# GrappleRobot_ControlBoard_V1_0.net
KiCad netlist of a schematic drawn in Altium Designer
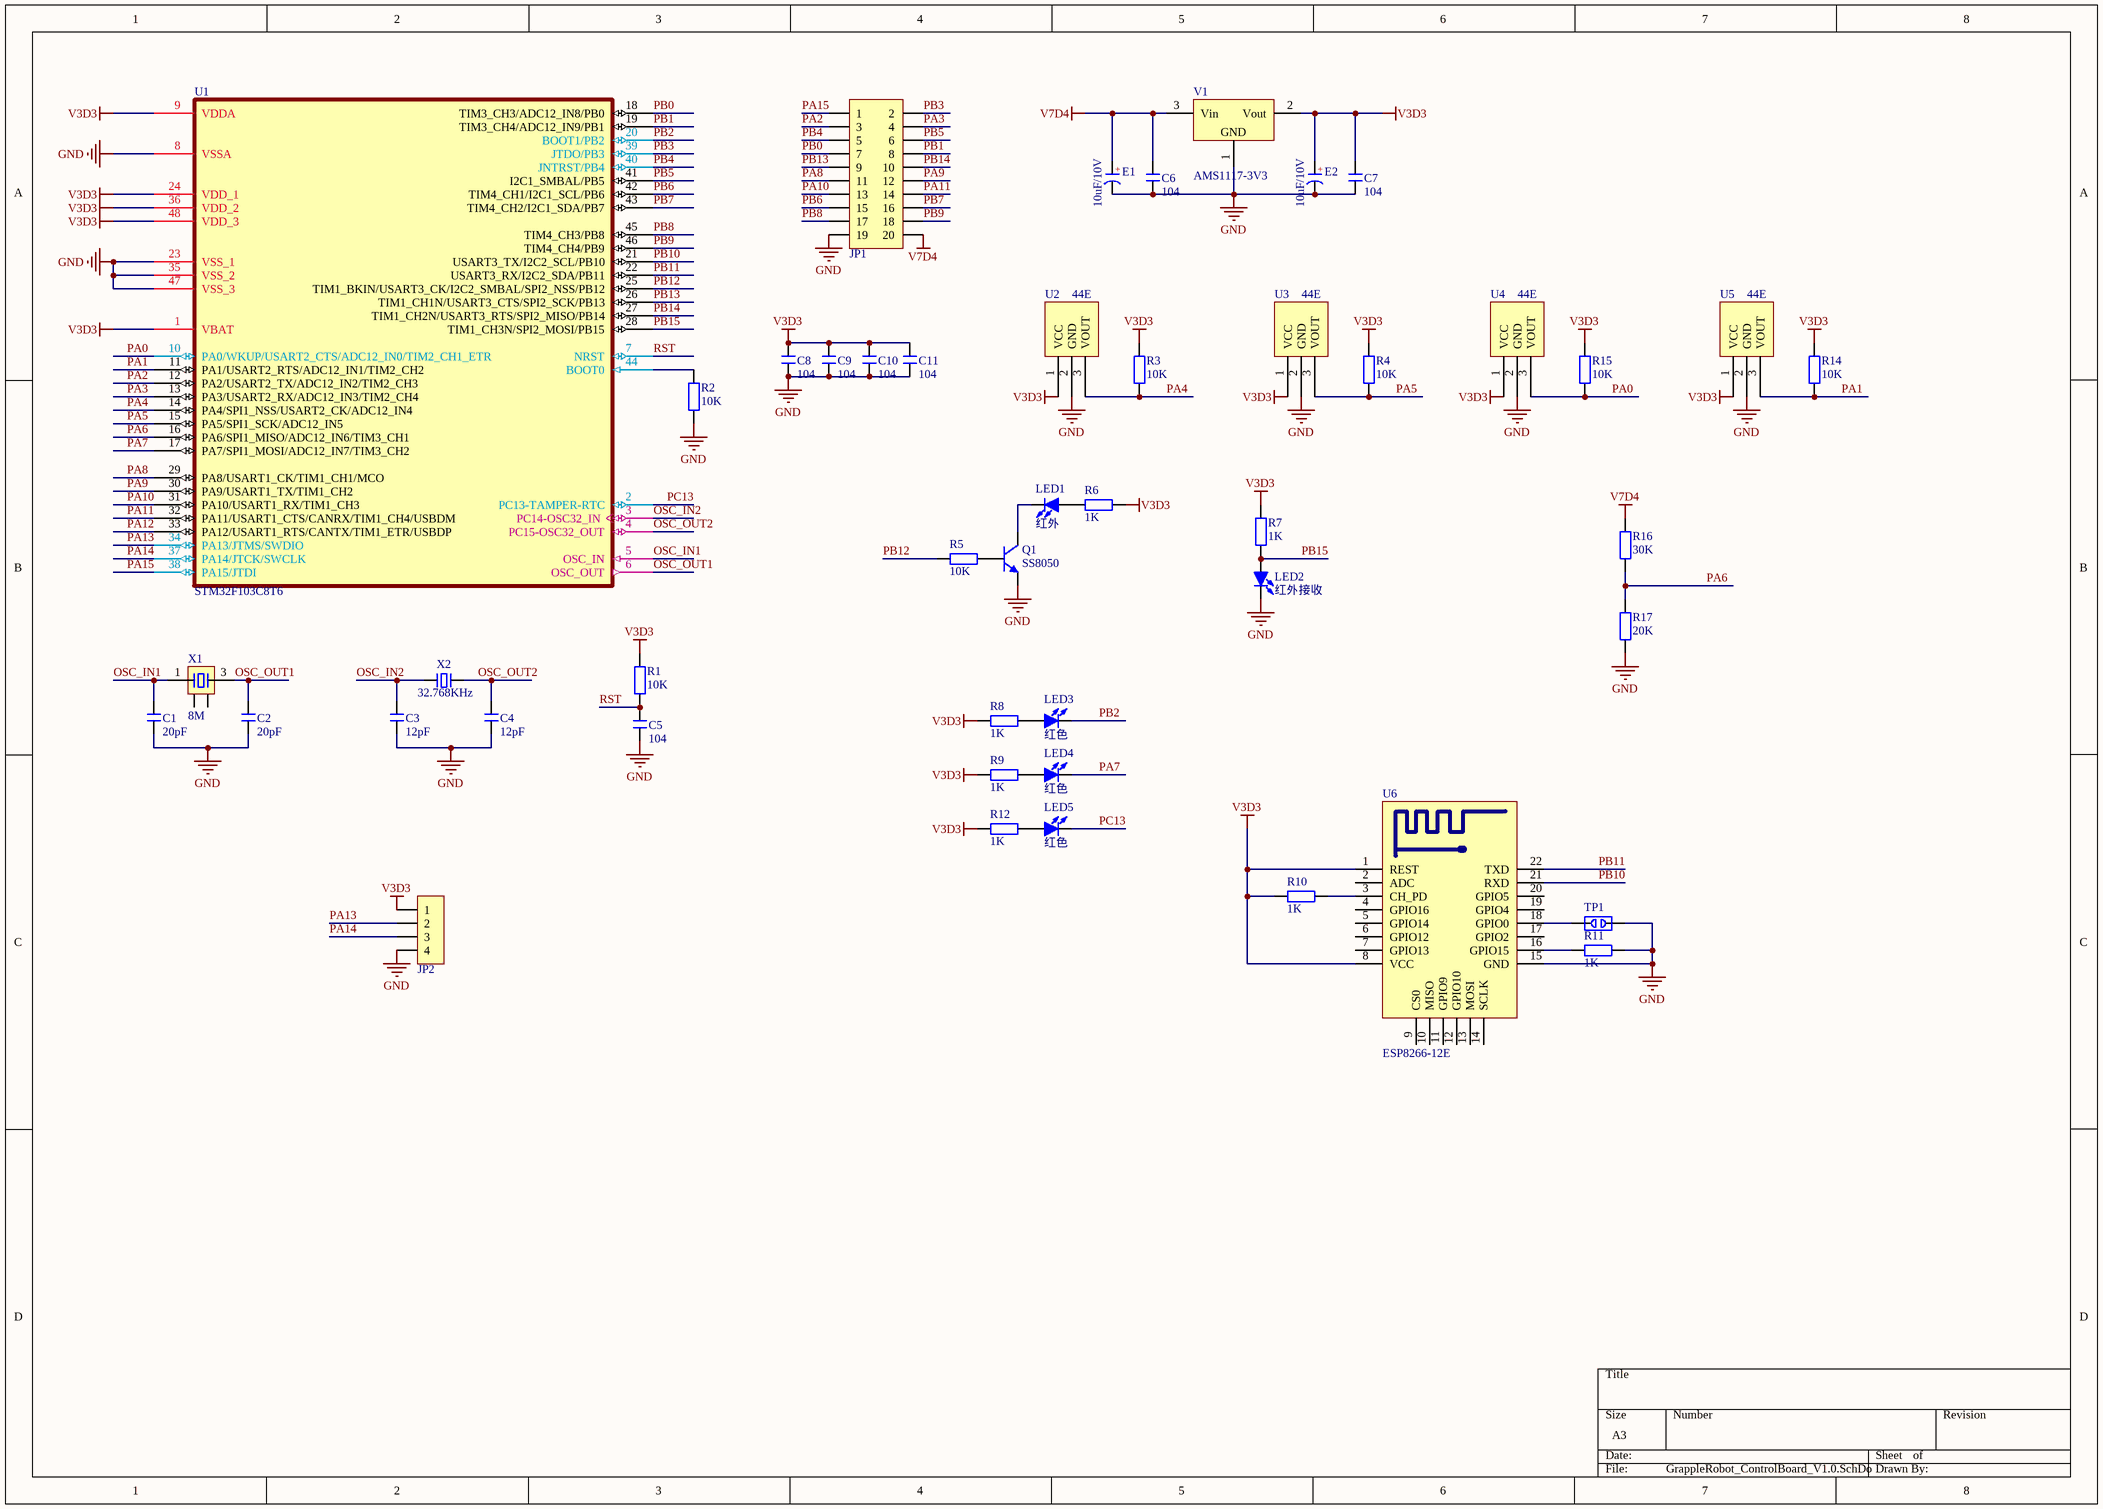
[diagram p0: GrappleRobot_ControlBoard_V1.0.SchDoc]

(export (version "E")
  (design (tool "Eeschema 10.0.6"))
  (components
    (comp (ref "C1")
      (value "20pF")
      (footprint "C 0603")
      (description "无极性贴片电容")
      (fields (field (name "版权归属") "黎明电子style"))
      (libsource (lib "电阻-电容-电感") (part "C"))
    )
    (comp (ref "C2")
      (value "20pF")
      (footprint "C 0603")
      (description "无极性贴片电容")
      (fields (field (name "版权归属") "黎明电子style"))
      (libsource (lib "电阻-电容-电感") (part "C"))
    )
    (comp (ref "C3")
      (value "12pF")
      (footprint "C 0603")
      (description "无极性贴片电容")
      (fields (field (name "版权归属") "黎明电子style"))
      (libsource (lib "电阻-电容-电感") (part "C"))
    )
    (comp (ref "C4")
      (value "12pF")
      (footprint "C 0603")
      (description "无极性贴片电容")
      (fields (field (name "版权归属") "黎明电子style"))
      (libsource (lib "电阻-电容-电感") (part "C"))
    )
    (comp (ref "C5")
      (value "104")
      (footprint "C 0603")
      (description "无极性贴片电容")
      (fields (field (name "版权归属") "黎明电子style"))
      (libsource (lib "电阻-电容-电感") (part "C"))
    )
    (comp (ref "C6")
      (value "104")
      (footprint "C 0603")
      (description "无极性贴片电容")
      (fields (field (name "版权归属") "黎明电子style"))
      (libsource (lib "电阻-电容-电感") (part "C"))
    )
    (comp (ref "C7")
      (value "104")
      (footprint "C 0603")
      (description "无极性贴片电容")
      (fields (field (name "版权归属") "黎明电子style"))
      (libsource (lib "电阻-电容-电感") (part "C"))
    )
    (comp (ref "C8")
      (value "104")
      (footprint "C 0603")
      (description "无极性贴片电容")
      (fields (field (name "版权归属") "黎明电子style"))
      (libsource (lib "电阻-电容-电感") (part "C"))
    )
    (comp (ref "C9")
      (value "104")
      (footprint "C 0603")
      (description "无极性贴片电容")
      (fields (field (name "版权归属") "黎明电子style"))
      (libsource (lib "电阻-电容-电感") (part "C"))
    )
    (comp (ref "C10")
      (value "104")
      (footprint "C 0603")
      (description "无极性贴片电容")
      (fields (field (name "版权归属") "黎明电子style"))
      (libsource (lib "电阻-电容-电感") (part "C"))
    )
    (comp (ref "C11")
      (value "104")
      (footprint "C 0603")
      (description "无极性贴片电容")
      (fields (field (name "版权归属") "黎明电子style"))
      (libsource (lib "电阻-电容-电感") (part "C"))
    )
    (comp (ref "E1")
      (value "10uF/10V")
      (footprint "C 1206")
      (description "贴片电解电容")
      (fields (field (name "版权归属") "黎明电子style"))
      (libsource (lib "电阻-电容-电感") (part "C-CM"))
    )
    (comp (ref "E2")
      (value "10uF/10V")
      (footprint "C 1206")
      (description "贴片电解电容")
      (fields (field (name "版权归属") "黎明电子style"))
      (libsource (lib "电阻-电容-电感") (part "C-CM"))
    )
    (comp (ref "JP1")
      (value "Header 2X10")
      (footprint "HDR-10X2")
      (description "10*2P接插件")
      (fields (field (name "版权归属") "黎明电子style"))
      (libsource (lib "接插件") (part "Header 10X2"))
    )
    (comp (ref "JP2")
      (value "HDR-1X4")
      (footprint "HDR-1X4")
      (description "4P接插件")
      (fields (field (name "版权归属") "黎明电子style"))
      (libsource (lib "接插件") (part "Header 4"))
    )
    (comp (ref "LED1")
      (value "红外")
      (footprint "LED 5MM-B")
      (description "5mm插件LED")
      (fields (field (name "版权归属") "黎明电子style"))
      (libsource (lib "LED") (part "LED-5MM"))
    )
    (comp (ref "LED2")
      (value "红外接收")
      (footprint "LED 5MM-B")
      (description "5mm插件LED")
      (fields (field (name "版权归属") "黎明电子style"))
      (libsource (lib "LED") (part "LED-5MM"))
    )
    (comp (ref "LED3")
      (value "红色")
      (footprint "LED 0603R")
      (description "5mm插件LED")
      (fields (field (name "版权归属") "黎明电子style"))
      (libsource (lib "LED") (part "LED-5MM"))
    )
    (comp (ref "LED4")
      (value "红色")
      (footprint "LED 0603R")
      (description "5mm插件LED")
      (fields (field (name "版权归属") "黎明电子style"))
      (libsource (lib "LED") (part "LED-5MM"))
    )
    (comp (ref "LED5")
      (value "红色")
      (footprint "LED 0603R")
      (description "5mm插件LED")
      (fields (field (name "版权归属") "黎明电子style"))
      (libsource (lib "LED") (part "LED-5MM"))
    )
    (comp (ref "Q1")
      (value "SS8050")
      (footprint "SOT23-3N")
      (description "高频放大-NPN型")
      (fields (field (name "版权归属") "黎明电子style"))
      (libsource (lib "三极管") (part "8050-SMD"))
    )
    (comp (ref "R1")
      (value "10K")
      (footprint "R 0603")
      (description "贴片电阻")
      (fields (field (name "版权归属") "黎明电子style"))
      (libsource (lib "电阻-电容-电感") (part "R"))
    )
    (comp (ref "R2")
      (value "10K")
      (footprint "R 0603")
      (description "贴片电阻")
      (fields (field (name "版权归属") "黎明电子style"))
      (libsource (lib "电阻-电容-电感") (part "R"))
    )
    (comp (ref "R3")
      (value "10K")
      (footprint "R 0603")
      (description "贴片电阻")
      (fields (field (name "版权归属") "黎明电子style"))
      (libsource (lib "电阻-电容-电感") (part "R"))
    )
    (comp (ref "R4")
      (value "10K")
      (footprint "R 0603")
      (description "贴片电阻")
      (fields (field (name "版权归属") "黎明电子style"))
      (libsource (lib "电阻-电容-电感") (part "R"))
    )
    (comp (ref "R5")
      (value "10K")
      (footprint "R 0603")
      (description "贴片电阻")
      (fields (field (name "版权归属") "黎明电子style"))
      (libsource (lib "电阻-电容-电感") (part "R"))
    )
    (comp (ref "R6")
      (value "1K")
      (footprint "R 0603")
      (description "贴片电阻")
      (fields (field (name "版权归属") "黎明电子style"))
      (libsource (lib "电阻-电容-电感") (part "R"))
    )
    (comp (ref "R7")
      (value "1K")
      (footprint "R 0603")
      (description "贴片电阻")
      (fields (field (name "版权归属") "黎明电子style"))
      (libsource (lib "电阻-电容-电感") (part "R"))
    )
    (comp (ref "R8")
      (value "1K")
      (footprint "R 0603")
      (description "贴片电阻")
      (fields (field (name "版权归属") "黎明电子style"))
      (libsource (lib "电阻-电容-电感") (part "R"))
    )
    (comp (ref "R9")
      (value "1K")
      (footprint "R 0603")
      (description "贴片电阻")
      (fields (field (name "版权归属") "黎明电子style"))
      (libsource (lib "电阻-电容-电感") (part "R"))
    )
    (comp (ref "R10")
      (value "1K")
      (footprint "R 0603")
      (description "贴片电阻")
      (fields (field (name "版权归属") "黎明电子style"))
      (libsource (lib "电阻-电容-电感") (part "R"))
    )
    (comp (ref "R11")
      (value "1K")
      (footprint "R 0603")
      (description "贴片电阻")
      (fields (field (name "版权归属") "黎明电子style"))
      (libsource (lib "电阻-电容-电感") (part "R"))
    )
    (comp (ref "R12")
      (value "1K")
      (footprint "R 0603")
      (description "贴片电阻")
      (fields (field (name "版权归属") "黎明电子style"))
      (libsource (lib "电阻-电容-电感") (part "R"))
    )
    (comp (ref "R14")
      (value "10K")
      (footprint "R 0603")
      (description "贴片电阻")
      (fields (field (name "版权归属") "黎明电子style"))
      (libsource (lib "电阻-电容-电感") (part "R"))
    )
    (comp (ref "R15")
      (value "10K")
      (footprint "R 0603")
      (description "贴片电阻")
      (fields (field (name "版权归属") "黎明电子style"))
      (libsource (lib "电阻-电容-电感") (part "R"))
    )
    (comp (ref "R16")
      (value "30K")
      (footprint "R 0603")
      (description "贴片电阻")
      (fields (field (name "版权归属") "黎明电子style"))
      (libsource (lib "电阻-电容-电感") (part "R"))
    )
    (comp (ref "R17")
      (value "20K")
      (footprint "R 0603")
      (description "贴片电阻")
      (fields (field (name "版权归属") "黎明电子style"))
      (libsource (lib "电阻-电容-电感") (part "R"))
    )
    (comp (ref "TP1")
      (value "~")
      (footprint "DEBUG PAD2")
      (description "调试断点焊盘")
      (fields (field (name "版权归属") "黎明电子style"))
      (libsource (lib "未分类器件") (part "DEBUG"))
    )
    (comp (ref "U1")
      (value "STM32F103C8T6")
      (footprint "stm8&stm32:LQFP48")
      (description "STM32 ARM-based 32-bit MCU with 64 Kbytes Flash, 48-pin LQFP, Industrial Temperature")
      (fields (field (name "PUBLISHER") "*"))
      (libsource (lib "stm8&stm32") (part "STM32F103C8T6"))
    )
    (comp (ref "U2") (value "44E") (footprint "SOT23-3N") (libsource (lib "LoveX") (part "44E")))
    (comp (ref "U3") (value "44E") (footprint "SOT23-3N") (libsource (lib "LoveX") (part "44E")))
    (comp (ref "U4") (value "44E") (footprint "SOT23-3N") (libsource (lib "LoveX") (part "44E")))
    (comp (ref "U5") (value "44E") (footprint "SOT23-3N") (libsource (lib "LoveX") (part "44E")))
    (comp (ref "U6")
      (value "ESP8266-12E")
      (footprint "ESP_12E")
      (description "串口 WIFI模块，ESP-12E")
      (fields (field (name "版权归属") "黎明电子style"))
      (libsource (lib "模块") (part "ESP8266-12E"))
    )
    (comp (ref "V1")
      (value "AMS1117-3V3")
      (footprint "SOT223_N")
      (description "三端稳压芯片")
      (fields (field (name "版权归属") "黎明电子style"))
      (libsource (lib "IC芯片") (part "AMS1117"))
    )
    (comp (ref "X1")
      (value "8M")
      (footprint "XTAL-5032")
      (description "4脚晶振")
      (fields (field (name "版权归属") "黎明电子style"))
      (libsource (lib "保险丝-晶振") (part "XTAL-4"))
    )
    (comp (ref "X2")
      (value "32.768KHz")
      (footprint "XTAL-3215")
      (description "2脚晶振")
      (fields (field (name "版权归属") "黎明电子style"))
      (libsource (lib "保险丝-晶振") (part "XTAL-2"))
    )
  )
  (nets
    (net (code "1") (name "/OSC_IN1") (class "Default")
      (node (ref "C1") (pin "2") (pinfunction "2_2") (pintype "passive"))
      (node (ref "U1") (pin "5") (pinfunction "OSC_IN_5") (pintype "input"))
      (node (ref "X1") (pin "1") (pinfunction "1_1") (pintype "passive"))
    )
    (net (code "2") (name "/OSC_IN2") (class "Default")
      (node (ref "C3") (pin "2") (pinfunction "2_2") (pintype "passive"))
      (node (ref "U1") (pin "3") (pinfunction "PC14-OSC32_IN_3") (pintype "bidirectional"))
      (node (ref "X2") (pin "1") (pinfunction "1_1") (pintype "passive"))
    )
    (net (code "3") (name "/OSC_OUT1") (class "Default")
      (node (ref "C2") (pin "2") (pinfunction "2_2") (pintype "passive"))
      (node (ref "U1") (pin "6") (pinfunction "OSC_OUT_6") (pintype "output"))
      (node (ref "X1") (pin "3") (pinfunction "3_3") (pintype "passive"))
    )
    (net (code "4") (name "/OSC_OUT2") (class "Default")
      (node (ref "C4") (pin "2") (pinfunction "2_2") (pintype "passive"))
      (node (ref "U1") (pin "4") (pinfunction "PC15-OSC32_OUT_4") (pintype "bidirectional"))
      (node (ref "X2") (pin "2") (pinfunction "2_2") (pintype "passive"))
    )
    (net (code "5") (name "/PA0") (class "Default")
      (node (ref "R15") (pin "1") (pinfunction "1_1") (pintype "passive"))
      (node (ref "U1") (pin "10") (pinfunction "PA0/WKUP/USART2_CTS/ADC12_IN0/TIM2_CH1_ETR_10") (pintype "bidirectional"))
      (node (ref "U4") (pin "3") (pinfunction "VOUT_3") (pintype "passive"))
    )
    (net (code "6") (name "/PA1") (class "Default")
      (node (ref "R14") (pin "1") (pinfunction "1_1") (pintype "passive"))
      (node (ref "U1") (pin "11") (pinfunction "PA1/USART2_RTS/ADC12_IN1/TIM2_CH2_11") (pintype "bidirectional"))
      (node (ref "U5") (pin "3") (pinfunction "VOUT_3") (pintype "passive"))
    )
    (net (code "7") (name "/PA2") (class "Default")
      (node (ref "JP1") (pin "3") (pinfunction "3_3") (pintype "passive"))
      (node (ref "U1") (pin "12") (pinfunction "PA2/USART2_TX/ADC12_IN2/TIM2_CH3_12") (pintype "bidirectional"))
    )
    (net (code "8") (name "/PA3") (class "Default")
      (node (ref "JP1") (pin "4") (pinfunction "4_4") (pintype "passive"))
      (node (ref "U1") (pin "13") (pinfunction "PA3/USART2_RX/ADC12_IN3/TIM2_CH4_13") (pintype "bidirectional"))
    )
    (net (code "9") (name "/PA4") (class "Default")
      (node (ref "R3") (pin "1") (pinfunction "1_1") (pintype "passive"))
      (node (ref "U1") (pin "14") (pinfunction "PA4/SPI1_NSS/USART2_CK/ADC12_IN4_14") (pintype "bidirectional"))
      (node (ref "U2") (pin "3") (pinfunction "VOUT_3") (pintype "passive"))
    )
    (net (code "10") (name "/PA5") (class "Default")
      (node (ref "R4") (pin "1") (pinfunction "1_1") (pintype "passive"))
      (node (ref "U1") (pin "15") (pinfunction "PA5/SPI1_SCK/ADC12_IN5_15") (pintype "bidirectional"))
      (node (ref "U3") (pin "3") (pinfunction "VOUT_3") (pintype "passive"))
    )
    (net (code "11") (name "/PA6") (class "Default")
      (node (ref "R16") (pin "2") (pinfunction "2_2") (pintype "passive"))
      (node (ref "R17") (pin "1") (pinfunction "1_1") (pintype "passive"))
      (node (ref "U1") (pin "16") (pinfunction "PA6/SPI1_MISO/ADC12_IN6/TIM3_CH1_16") (pintype "bidirectional"))
    )
    (net (code "12") (name "/PA7") (class "Default")
      (node (ref "LED4") (pin "2") (pinfunction "K_2") (pintype "passive"))
      (node (ref "U1") (pin "17") (pinfunction "PA7/SPI1_MOSI/ADC12_IN7/TIM3_CH2_17") (pintype "bidirectional"))
    )
    (net (code "13") (name "/PA8") (class "Default")
      (node (ref "JP1") (pin "11") (pinfunction "11_11") (pintype "passive"))
      (node (ref "U1") (pin "29") (pinfunction "PA8/USART1_CK/TIM1_CH1/MCO_29") (pintype "bidirectional"))
    )
    (net (code "14") (name "/PA9") (class "Default")
      (node (ref "JP1") (pin "12") (pinfunction "12_12") (pintype "passive"))
      (node (ref "U1") (pin "30") (pinfunction "PA9/USART1_TX/TIM1_CH2_30") (pintype "bidirectional"))
    )
    (net (code "15") (name "/PA10") (class "Default")
      (node (ref "JP1") (pin "13") (pinfunction "13_13") (pintype "passive"))
      (node (ref "U1") (pin "31") (pinfunction "PA10/USART1_RX/TIM1_CH3_31") (pintype "bidirectional"))
    )
    (net (code "16") (name "/PA11") (class "Default")
      (node (ref "JP1") (pin "14") (pinfunction "14_14") (pintype "passive"))
      (node (ref "U1") (pin "32") (pinfunction "PA11/USART1_CTS/CANRX/TIM1_CH4/USBDM_32") (pintype "bidirectional"))
    )
    (net (code "17") (name "/PA12") (class "Default")
      (node (ref "U1") (pin "33") (pinfunction "PA12/USART1_RTS/CANTX/TIM1_ETR/USBDP_33") (pintype "bidirectional"))
    )
    (net (code "18") (name "/PA13") (class "Default")
      (node (ref "JP2") (pin "2") (pinfunction "2_2") (pintype "passive"))
      (node (ref "U1") (pin "34") (pinfunction "PA13/JTMS/SWDIO_34") (pintype "bidirectional"))
    )
    (net (code "19") (name "/PA14") (class "Default")
      (node (ref "JP2") (pin "3") (pinfunction "3_3") (pintype "passive"))
      (node (ref "U1") (pin "37") (pinfunction "PA14/JTCK/SWCLK_37") (pintype "bidirectional"))
    )
    (net (code "20") (name "/PA15") (class "Default")
      (node (ref "JP1") (pin "1") (pinfunction "1_1") (pintype "passive"))
      (node (ref "U1") (pin "38") (pinfunction "PA15/JTDI_38") (pintype "bidirectional"))
    )
    (net (code "21") (name "/PB0") (class "Default")
      (node (ref "JP1") (pin "7") (pinfunction "7_7") (pintype "passive"))
      (node (ref "U1") (pin "18") (pinfunction "TIM3_CH3/ADC12_IN8/PB0_18") (pintype "bidirectional"))
    )
    (net (code "22") (name "/PB1") (class "Default")
      (node (ref "JP1") (pin "8") (pinfunction "8_8") (pintype "passive"))
      (node (ref "U1") (pin "19") (pinfunction "TIM3_CH4/ADC12_IN9/PB1_19") (pintype "bidirectional"))
    )
    (net (code "23") (name "/PB2") (class "Default")
      (node (ref "LED3") (pin "2") (pinfunction "K_2") (pintype "passive"))
      (node (ref "U1") (pin "20") (pinfunction "BOOT1/PB2_20") (pintype "bidirectional"))
    )
    (net (code "24") (name "/PB3") (class "Default")
      (node (ref "JP1") (pin "2") (pinfunction "2_2") (pintype "passive"))
      (node (ref "U1") (pin "39") (pinfunction "JTDO/PB3_39") (pintype "bidirectional"))
    )
    (net (code "25") (name "/PB4") (class "Default")
      (node (ref "JP1") (pin "5") (pinfunction "5_5") (pintype "passive"))
      (node (ref "U1") (pin "40") (pinfunction "JNTRST/PB4_40") (pintype "bidirectional"))
    )
    (net (code "26") (name "/PB5") (class "Default")
      (node (ref "JP1") (pin "6") (pinfunction "6_6") (pintype "passive"))
      (node (ref "U1") (pin "41") (pinfunction "I2C1_SMBAL/PB5_41") (pintype "bidirectional"))
    )
    (net (code "27") (name "/PB6") (class "Default")
      (node (ref "JP1") (pin "15") (pinfunction "15_15") (pintype "passive"))
      (node (ref "U1") (pin "42") (pinfunction "TIM4_CH1/I2C1_SCL/PB6_42") (pintype "bidirectional"))
    )
    (net (code "28") (name "/PB7") (class "Default")
      (node (ref "JP1") (pin "16") (pinfunction "16_16") (pintype "passive"))
      (node (ref "U1") (pin "43") (pinfunction "TIM4_CH2/I2C1_SDA/PB7_43") (pintype "bidirectional"))
    )
    (net (code "29") (name "/PB8") (class "Default")
      (node (ref "JP1") (pin "17") (pinfunction "17_17") (pintype "passive"))
      (node (ref "U1") (pin "45") (pinfunction "TIM4_CH3/PB8_45") (pintype "bidirectional"))
    )
    (net (code "30") (name "/PB9") (class "Default")
      (node (ref "JP1") (pin "18") (pinfunction "18_18") (pintype "passive"))
      (node (ref "U1") (pin "46") (pinfunction "TIM4_CH4/PB9_46") (pintype "bidirectional"))
    )
    (net (code "31") (name "/PB10") (class "Default")
      (node (ref "U1") (pin "21") (pinfunction "USART3_TX/I2C2_SCL/PB10_21") (pintype "bidirectional"))
      (node (ref "U6") (pin "21") (pinfunction "RXD_21") (pintype "passive"))
    )
    (net (code "32") (name "/PB11") (class "Default")
      (node (ref "U1") (pin "22") (pinfunction "USART3_RX/I2C2_SDA/PB11_22") (pintype "bidirectional"))
      (node (ref "U6") (pin "22") (pinfunction "TXD_22") (pintype "passive"))
    )
    (net (code "33") (name "/PB12") (class "Default")
      (node (ref "R5") (pin "2") (pinfunction "2_2") (pintype "passive"))
      (node (ref "U1") (pin "25") (pinfunction "TIM1_BKIN/USART3_CK/I2C2_SMBAL/SPI2_NSS/PB12_25") (pintype "bidirectional"))
    )
    (net (code "34") (name "/PB13") (class "Default")
      (node (ref "JP1") (pin "9") (pinfunction "9_9") (pintype "passive"))
      (node (ref "U1") (pin "26") (pinfunction "TIM1_CH1N/USART3_CTS/SPI2_SCK/PB13_26") (pintype "bidirectional"))
    )
    (net (code "35") (name "/PB14") (class "Default")
      (node (ref "JP1") (pin "10") (pinfunction "10_10") (pintype "passive"))
      (node (ref "U1") (pin "27") (pinfunction "TIM1_CH2N/USART3_RTS/SPI2_MISO/PB14_27") (pintype "bidirectional"))
    )
    (net (code "36") (name "/PB15") (class "Default")
      (node (ref "LED2") (pin "1") (pinfunction "A_1") (pintype "passive"))
      (node (ref "R7") (pin "2") (pinfunction "2_2") (pintype "passive"))
      (node (ref "U1") (pin "28") (pinfunction "TIM1_CH3N/SPI2_MOSI/PB15_28") (pintype "bidirectional"))
    )
    (net (code "37") (name "/PC13") (class "Default")
      (node (ref "LED5") (pin "2") (pinfunction "K_2") (pintype "passive"))
      (node (ref "U1") (pin "2") (pinfunction "PC13-TAMPER-RTC_2") (pintype "bidirectional"))
    )
    (net (code "38") (name "/RST") (class "Default")
      (node (ref "C5") (pin "2") (pinfunction "2_2") (pintype "passive"))
      (node (ref "R1") (pin "1") (pinfunction "1_1") (pintype "passive"))
      (node (ref "U1") (pin "7") (pinfunction "NRST_7") (pintype "bidirectional"))
    )
    (net (code "39") (name "GND") (class "Default")
      (node (ref "C1") (pin "1") (pinfunction "1_1") (pintype "passive"))
      (node (ref "C10") (pin "1") (pinfunction "1_1") (pintype "passive"))
      (node (ref "C11") (pin "1") (pinfunction "1_1") (pintype "passive"))
      (node (ref "C2") (pin "1") (pinfunction "1_1") (pintype "passive"))
      (node (ref "C3") (pin "1") (pinfunction "1_1") (pintype "passive"))
      (node (ref "C4") (pin "1") (pinfunction "1_1") (pintype "passive"))
      (node (ref "C5") (pin "1") (pinfunction "1_1") (pintype "passive"))
      (node (ref "C6") (pin "1") (pinfunction "1_1") (pintype "passive"))
      (node (ref "C7") (pin "1") (pinfunction "1_1") (pintype "passive"))
      (node (ref "C8") (pin "1") (pinfunction "1_1") (pintype "passive"))
      (node (ref "C9") (pin "1") (pinfunction "1_1") (pintype "passive"))
      (node (ref "E1") (pin "2") (pinfunction "K_2") (pintype "passive"))
      (node (ref "E2") (pin "2") (pinfunction "K_2") (pintype "passive"))
      (node (ref "JP1") (pin "19") (pinfunction "19_19") (pintype "passive"))
      (node (ref "JP2") (pin "4") (pinfunction "4_4") (pintype "passive"))
      (node (ref "LED2") (pin "2") (pinfunction "K_2") (pintype "passive"))
      (node (ref "Q1") (pin "2") (pinfunction "E_2") (pintype "passive"))
      (node (ref "R11") (pin "2") (pinfunction "2_2") (pintype "passive"))
      (node (ref "R17") (pin "2") (pinfunction "2_2") (pintype "passive"))
      (node (ref "R2") (pin "1") (pinfunction "1_1") (pintype "passive"))
      (node (ref "TP1") (pin "2") (pinfunction "2_2") (pintype "passive"))
      (node (ref "U1") (pin "23") (pinfunction "VSS_1_23") (pintype "power_in"))
      (node (ref "U1") (pin "35") (pinfunction "VSS_2_35") (pintype "power_in"))
      (node (ref "U1") (pin "47") (pinfunction "VSS_3_47") (pintype "power_in"))
      (node (ref "U1") (pin "8") (pinfunction "VSSA_8") (pintype "power_in"))
      (node (ref "U2") (pin "2") (pinfunction "GND_2") (pintype "passive"))
      (node (ref "U3") (pin "2") (pinfunction "GND_2") (pintype "passive"))
      (node (ref "U4") (pin "2") (pinfunction "GND_2") (pintype "passive"))
      (node (ref "U5") (pin "2") (pinfunction "GND_2") (pintype "passive"))
      (node (ref "U6") (pin "15") (pinfunction "GND_15") (pintype "passive"))
      (node (ref "V1") (pin "1") (pinfunction "GND_1") (pintype "passive"))
    )
    (net (code "40") (name "Net-(LED1-A)") (class "Default")
      (node (ref "LED1") (pin "1") (pinfunction "A_1") (pintype "passive"))
      (node (ref "R6") (pin "2") (pinfunction "2_2") (pintype "passive"))
    )
    (net (code "41") (name "Net-(LED1-K)") (class "Default")
      (node (ref "LED1") (pin "2") (pinfunction "K_2") (pintype "passive"))
      (node (ref "Q1") (pin "3") (pinfunction "C_3") (pintype "passive"))
    )
    (net (code "42") (name "Net-(LED3-A)") (class "Default")
      (node (ref "LED3") (pin "1") (pinfunction "A_1") (pintype "passive"))
      (node (ref "R8") (pin "2") (pinfunction "2_2") (pintype "passive"))
    )
    (net (code "43") (name "Net-(LED4-A)") (class "Default")
      (node (ref "LED4") (pin "1") (pinfunction "A_1") (pintype "passive"))
      (node (ref "R9") (pin "2") (pinfunction "2_2") (pintype "passive"))
    )
    (net (code "44") (name "Net-(LED5-A)") (class "Default")
      (node (ref "LED5") (pin "1") (pinfunction "A_1") (pintype "passive"))
      (node (ref "R12") (pin "2") (pinfunction "2_2") (pintype "passive"))
    )
    (net (code "45") (name "Net-(Q1-B)") (class "Default")
      (node (ref "Q1") (pin "1") (pinfunction "B_1") (pintype "passive"))
      (node (ref "R5") (pin "1") (pinfunction "1_1") (pintype "passive"))
    )
    (net (code "46") (name "Net-(U1-BOOT0)") (class "Default")
      (node (ref "R2") (pin "2") (pinfunction "2_2") (pintype "passive"))
      (node (ref "U1") (pin "44") (pinfunction "BOOT0_44") (pintype "input"))
    )
    (net (code "47") (name "Net-(U6-CH_PD)") (class "Default")
      (node (ref "R10") (pin "2") (pinfunction "2_2") (pintype "passive"))
      (node (ref "U6") (pin "3") (pinfunction "CH_PD_3") (pintype "passive"))
    )
    (net (code "48") (name "Net-(U6-GPIO0)") (class "Default")
      (node (ref "TP1") (pin "1") (pinfunction "1_1") (pintype "passive"))
      (node (ref "U6") (pin "18") (pinfunction "GPIO0_18") (pintype "passive"))
    )
    (net (code "49") (name "Net-(U6-GPIO15)") (class "Default")
      (node (ref "R11") (pin "1") (pinfunction "1_1") (pintype "passive"))
      (node (ref "U6") (pin "16") (pinfunction "GPIO15_16") (pintype "passive"))
    )
    (net (code "50") (name "V3D3") (class "Default")
      (node (ref "C10") (pin "2") (pinfunction "2_2") (pintype "passive"))
      (node (ref "C11") (pin "2") (pinfunction "2_2") (pintype "passive"))
      (node (ref "C7") (pin "2") (pinfunction "2_2") (pintype "passive"))
      (node (ref "C8") (pin "2") (pinfunction "2_2") (pintype "passive"))
      (node (ref "C9") (pin "2") (pinfunction "2_2") (pintype "passive"))
      (node (ref "E2") (pin "1") (pinfunction "A_1") (pintype "passive"))
      (node (ref "JP2") (pin "1") (pinfunction "1_1") (pintype "passive"))
      (node (ref "R1") (pin "2") (pinfunction "2_2") (pintype "passive"))
      (node (ref "R10") (pin "1") (pinfunction "1_1") (pintype "passive"))
      (node (ref "R12") (pin "1") (pinfunction "1_1") (pintype "passive"))
      (node (ref "R14") (pin "2") (pinfunction "2_2") (pintype "passive"))
      (node (ref "R15") (pin "2") (pinfunction "2_2") (pintype "passive"))
      (node (ref "R3") (pin "2") (pinfunction "2_2") (pintype "passive"))
      (node (ref "R4") (pin "2") (pinfunction "2_2") (pintype "passive"))
      (node (ref "R6") (pin "1") (pinfunction "1_1") (pintype "passive"))
      (node (ref "R7") (pin "1") (pinfunction "1_1") (pintype "passive"))
      (node (ref "R8") (pin "1") (pinfunction "1_1") (pintype "passive"))
      (node (ref "R9") (pin "1") (pinfunction "1_1") (pintype "passive"))
      (node (ref "U1") (pin "1") (pinfunction "VBAT_1") (pintype "power_in"))
      (node (ref "U1") (pin "24") (pinfunction "VDD_1_24") (pintype "power_in"))
      (node (ref "U1") (pin "36") (pinfunction "VDD_2_36") (pintype "power_in"))
      (node (ref "U1") (pin "48") (pinfunction "VDD_3_48") (pintype "power_in"))
      (node (ref "U1") (pin "9") (pinfunction "VDDA_9") (pintype "power_in"))
      (node (ref "U2") (pin "1") (pinfunction "VCC_1") (pintype "passive"))
      (node (ref "U3") (pin "1") (pinfunction "VCC_1") (pintype "passive"))
      (node (ref "U4") (pin "1") (pinfunction "VCC_1") (pintype "passive"))
      (node (ref "U5") (pin "1") (pinfunction "VCC_1") (pintype "passive"))
      (node (ref "U6") (pin "1") (pinfunction "REST_1") (pintype "passive"))
      (node (ref "U6") (pin "8") (pinfunction "VCC_8") (pintype "passive"))
      (node (ref "V1") (pin "2") (pinfunction "Vout_2") (pintype "passive"))
    )
    (net (code "51") (name "V7D4") (class "Default")
      (node (ref "C6") (pin "2") (pinfunction "2_2") (pintype "passive"))
      (node (ref "E1") (pin "1") (pinfunction "A_1") (pintype "passive"))
      (node (ref "JP1") (pin "20") (pinfunction "20_20") (pintype "passive"))
      (node (ref "R16") (pin "1") (pinfunction "1_1") (pintype "passive"))
      (node (ref "V1") (pin "3") (pinfunction "Vin_3") (pintype "passive"))
    )
    (net (code "52") (name "unconnected-(U6-ADC-Pad2)") (class "Default")
      (node (ref "U6") (pin "2") (pinfunction "ADC_2") (pintype "passive"))
    )
    (net (code "53") (name "unconnected-(U6-CS0-Pad9)") (class "Default")
      (node (ref "U6") (pin "9") (pinfunction "CS0_9") (pintype "passive"))
    )
    (net (code "54") (name "unconnected-(U6-GPIO2-Pad17)") (class "Default")
      (node (ref "U6") (pin "17") (pinfunction "GPIO2_17") (pintype "passive"))
    )
    (net (code "55") (name "unconnected-(U6-GPIO4-Pad19)") (class "Default")
      (node (ref "U6") (pin "19") (pinfunction "GPIO4_19") (pintype "passive"))
    )
    (net (code "56") (name "unconnected-(U6-GPIO5-Pad20)") (class "Default")
      (node (ref "U6") (pin "20") (pinfunction "GPIO5_20") (pintype "passive"))
    )
    (net (code "57") (name "unconnected-(U6-GPIO9-Pad11)") (class "Default")
      (node (ref "U6") (pin "11") (pinfunction "GPIO9_11") (pintype "passive"))
    )
    (net (code "58") (name "unconnected-(U6-GPIO10-Pad12)") (class "Default")
      (node (ref "U6") (pin "12") (pinfunction "GPIO10_12") (pintype "passive"))
    )
    (net (code "59") (name "unconnected-(U6-GPIO12-Pad6)") (class "Default")
      (node (ref "U6") (pin "6") (pinfunction "GPIO12_6") (pintype "passive"))
    )
    (net (code "60") (name "unconnected-(U6-GPIO13-Pad7)") (class "Default")
      (node (ref "U6") (pin "7") (pinfunction "GPIO13_7") (pintype "passive"))
    )
    (net (code "61") (name "unconnected-(U6-GPIO14-Pad5)") (class "Default")
      (node (ref "U6") (pin "5") (pinfunction "GPIO14_5") (pintype "passive"))
    )
    (net (code "62") (name "unconnected-(U6-GPIO16-Pad4)") (class "Default")
      (node (ref "U6") (pin "4") (pinfunction "GPIO16_4") (pintype "passive"))
    )
    (net (code "63") (name "unconnected-(U6-MISO-Pad10)") (class "Default")
      (node (ref "U6") (pin "10") (pinfunction "MISO_10") (pintype "passive"))
    )
    (net (code "64") (name "unconnected-(U6-MOSI-Pad13)") (class "Default")
      (node (ref "U6") (pin "13") (pinfunction "MOSI_13") (pintype "passive"))
    )
    (net (code "65") (name "unconnected-(U6-SCLK-Pad14)") (class "Default")
      (node (ref "U6") (pin "14") (pinfunction "SCLK_14") (pintype "passive"))
    )
    (net (code "66") (name "unconnected-(X1-Pad2)") (class "Default")
      (node (ref "X1") (pin "2") (pinfunction "2_2") (pintype "passive"))
    )
    (net (code "67") (name "unconnected-(X1-Pad4)") (class "Default")
      (node (ref "X1") (pin "4") (pinfunction "4_4") (pintype "passive"))
    )
  )
)
